# CRG.net
KiCad netlist of a schematic drawn in Altium Designer
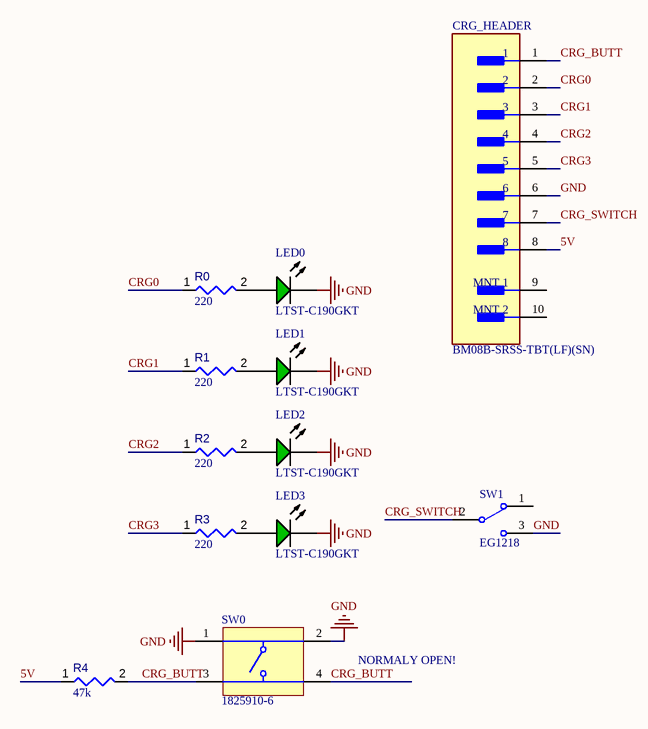
[diagram p0: CRG.SchDoc]

(export (version "E")
  (design (tool "Eeschema 10.0.6"))
  (components
    (comp (ref "CRG_HEADER")
      (value "BM08B-SRSS-TBT(LF)(SN)")
      (footprint "FP-BM08B-SRSS-TBT_LF_SN-MFG")
      (description "Conn Shrouded Header HDR 8 POS 1mm Solder ST SMD T/R / CONN HEADER SH 8POS TOP 1MM TIN")
      (libsource (lib "Evan Chang work on PCB") (part "98b5586d6b3804e276fbd0410cd4945"))
    )
    (comp (ref "LED0")
      (value "LTST-C190GKT")
      (footprint "LTST-C190GKT_V")
      (description "LED Uni-Color Green, 100 mW, 30 mA, -55 to 85 degC, 2-Pin SMD, RoHS, Tape and Reel")
      (fields (field (name "POWER") "100mW") (field (name "MANUFACTURER") "Lite-On"))
      (libsource (lib "Evan Chang work on PCB") (part "LED-GREEN-AK-2"))
    )
    (comp (ref "LED1")
      (value "LTST-C190GKT")
      (footprint "LTST-C190GKT_V")
      (description "LED Uni-Color Green, 100 mW, 30 mA, -55 to 85 degC, 2-Pin SMD, RoHS, Tape and Reel")
      (fields (field (name "POWER") "100mW") (field (name "MANUFACTURER") "Lite-On"))
      (libsource (lib "Evan Chang work on PCB") (part "LED-GREEN-AK-2"))
    )
    (comp (ref "LED2")
      (value "LTST-C190GKT")
      (footprint "LTST-C190GKT_V")
      (description "LED Uni-Color Green, 100 mW, 30 mA, -55 to 85 degC, 2-Pin SMD, RoHS, Tape and Reel")
      (fields (field (name "POWER") "100mW") (field (name "MANUFACTURER") "Lite-On"))
      (libsource (lib "Evan Chang work on PCB") (part "LED-GREEN-AK-2"))
    )
    (comp (ref "LED3")
      (value "LTST-C190GKT")
      (footprint "LTST-C190GKT_V")
      (description "LED Uni-Color Green, 100 mW, 30 mA, -55 to 85 degC, 2-Pin SMD, RoHS, Tape and Reel")
      (fields (field (name "POWER") "100mW") (field (name "MANUFACTURER") "Lite-On"))
      (libsource (lib "Evan Chang work on PCB") (part "LED-GREEN-AK-2"))
    )
    (comp (ref "R0")
      (value "220")
      (footprint "RESC1608X55X30LL20T10")
      (fields (field (name "TOLERANCE") "5%") (field (name "Comment") "RK73B1JTTD221J"))
      (libsource (lib "Evan Chang work on PCB") (part "RES-2"))
    )
    (comp (ref "R1")
      (value "220")
      (footprint "RESC1608X55X30LL20T10")
      (fields (field (name "TOLERANCE") "5%") (field (name "Comment") "RK73B1JTTD221J"))
      (libsource (lib "Evan Chang work on PCB") (part "RES-2"))
    )
    (comp (ref "R2")
      (value "220")
      (footprint "RESC1608X55X30LL20T10")
      (fields (field (name "TOLERANCE") "5%") (field (name "Comment") "RK73B1JTTD221J"))
      (libsource (lib "Evan Chang work on PCB") (part "RES-2"))
    )
    (comp (ref "R3")
      (value "220")
      (footprint "RESC1608X55X30LL20T10")
      (fields (field (name "TOLERANCE") "5%") (field (name "Comment") "RK73B1JTTD221J"))
      (libsource (lib "Evan Chang work on PCB") (part "RES-2"))
    )
    (comp (ref "R4")
      (value "47k")
      (footprint "RESC1005X40X25NL05T10")
      (fields (field (name "TOLERANCE") "1%") (field (name "Comment") "RC0402FR-0747KL"))
      (libsource (lib "Evan Chang work on PCB") (part "RES-2"))
    )
    (comp (ref "SW0")
      (value "1825910-6")
      (footprint "TECO-1825910-6_V")
      (libsource (lib "Evan Chang work on PCB") (part "SW-SPST-4_A"))
    )
    (comp (ref "SW1")
      (value "EG1218")
      (footprint "ESWI-EG1218_V")
      (description "Slide Switch, SPDT, 500 V, -20 to 70 degC, 3-Pin THD, RoHS, Bulk")
      (fields (field (name "MANUFACTURER") "E-Switch"))
      (libsource (lib "Evan Chang work on PCB") (part "SW-SPDT-3_B"))
    )
  )
  (nets
    (net (code "1") (name "/5V") (class "Default")
      (node (ref "CRG_HEADER") (pin "8") (pinfunction "8_8") (pintype "passive"))
      (node (ref "R4") (pin "1") (pinfunction "1_1") (pintype "passive"))
    )
    (net (code "2") (name "/CRG0") (class "Default")
      (node (ref "CRG_HEADER") (pin "2") (pinfunction "2_2") (pintype "passive"))
      (node (ref "R0") (pin "1") (pinfunction "1_1") (pintype "passive"))
    )
    (net (code "3") (name "/CRG1") (class "Default")
      (node (ref "CRG_HEADER") (pin "3") (pinfunction "3_3") (pintype "passive"))
      (node (ref "R1") (pin "1") (pinfunction "1_1") (pintype "passive"))
    )
    (net (code "4") (name "/CRG2") (class "Default")
      (node (ref "CRG_HEADER") (pin "4") (pinfunction "4_4") (pintype "passive"))
      (node (ref "R2") (pin "1") (pinfunction "1_1") (pintype "passive"))
    )
    (net (code "5") (name "/CRG3") (class "Default")
      (node (ref "CRG_HEADER") (pin "5") (pinfunction "5_5") (pintype "passive"))
      (node (ref "R3") (pin "1") (pinfunction "1_1") (pintype "passive"))
    )
    (net (code "6") (name "/CRG_BUTT") (class "Default")
      (node (ref "CRG_HEADER") (pin "1") (pinfunction "1_1") (pintype "passive"))
      (node (ref "R4") (pin "2") (pinfunction "2_2") (pintype "passive"))
      (node (ref "SW0") (pin "3") (pinfunction "3_3") (pintype "passive"))
      (node (ref "SW0") (pin "4") (pinfunction "4_4") (pintype "passive"))
    )
    (net (code "7") (name "/CRG_SWITCH") (class "Default")
      (node (ref "CRG_HEADER") (pin "7") (pinfunction "7_7") (pintype "passive"))
      (node (ref "SW1") (pin "2") (pinfunction "COM_2") (pintype "passive"))
    )
    (net (code "8") (name "GND") (class "Default")
      (node (ref "CRG_HEADER") (pin "6") (pinfunction "6_6") (pintype "passive"))
      (node (ref "LED0") (pin "2") (pinfunction "K_2") (pintype "passive"))
      (node (ref "LED1") (pin "2") (pinfunction "K_2") (pintype "passive"))
      (node (ref "LED2") (pin "2") (pinfunction "K_2") (pintype "passive"))
      (node (ref "LED3") (pin "2") (pinfunction "K_2") (pintype "passive"))
      (node (ref "SW0") (pin "1") (pinfunction "1_1") (pintype "passive"))
      (node (ref "SW0") (pin "2") (pinfunction "2_2") (pintype "passive"))
      (node (ref "SW1") (pin "3") (pinfunction "3_3") (pintype "passive"))
    )
    (net (code "9") (name "Net-(LED0-A)") (class "Default")
      (node (ref "LED0") (pin "1") (pinfunction "A_1") (pintype "passive"))
      (node (ref "R0") (pin "2") (pinfunction "2_2") (pintype "passive"))
    )
    (net (code "10") (name "Net-(LED1-A)") (class "Default")
      (node (ref "LED1") (pin "1") (pinfunction "A_1") (pintype "passive"))
      (node (ref "R1") (pin "2") (pinfunction "2_2") (pintype "passive"))
    )
    (net (code "11") (name "Net-(LED2-A)") (class "Default")
      (node (ref "LED2") (pin "1") (pinfunction "A_1") (pintype "passive"))
      (node (ref "R2") (pin "2") (pinfunction "2_2") (pintype "passive"))
    )
    (net (code "12") (name "Net-(LED3-A)") (class "Default")
      (node (ref "LED3") (pin "1") (pinfunction "A_1") (pintype "passive"))
      (node (ref "R3") (pin "2") (pinfunction "2_2") (pintype "passive"))
    )
    (net (code "13") (name "unconnected-(CRG_HEADER-MNT_1-Pad9)") (class "Default")
      (node (ref "CRG_HEADER") (pin "9") (pinfunction "MNT_1_9") (pintype "passive"))
    )
    (net (code "14") (name "unconnected-(CRG_HEADER-MNT_2-Pad10)") (class "Default")
      (node (ref "CRG_HEADER") (pin "10") (pinfunction "MNT_2_10") (pintype "passive"))
    )
    (net (code "15") (name "unconnected-(SW1-Pad1)") (class "Default")
      (node (ref "SW1") (pin "1") (pinfunction "1_1") (pintype "passive"))
    )
  )
)
